# ExpositionTest.net
KiCad netlist of a schematic drawn in EAGLE
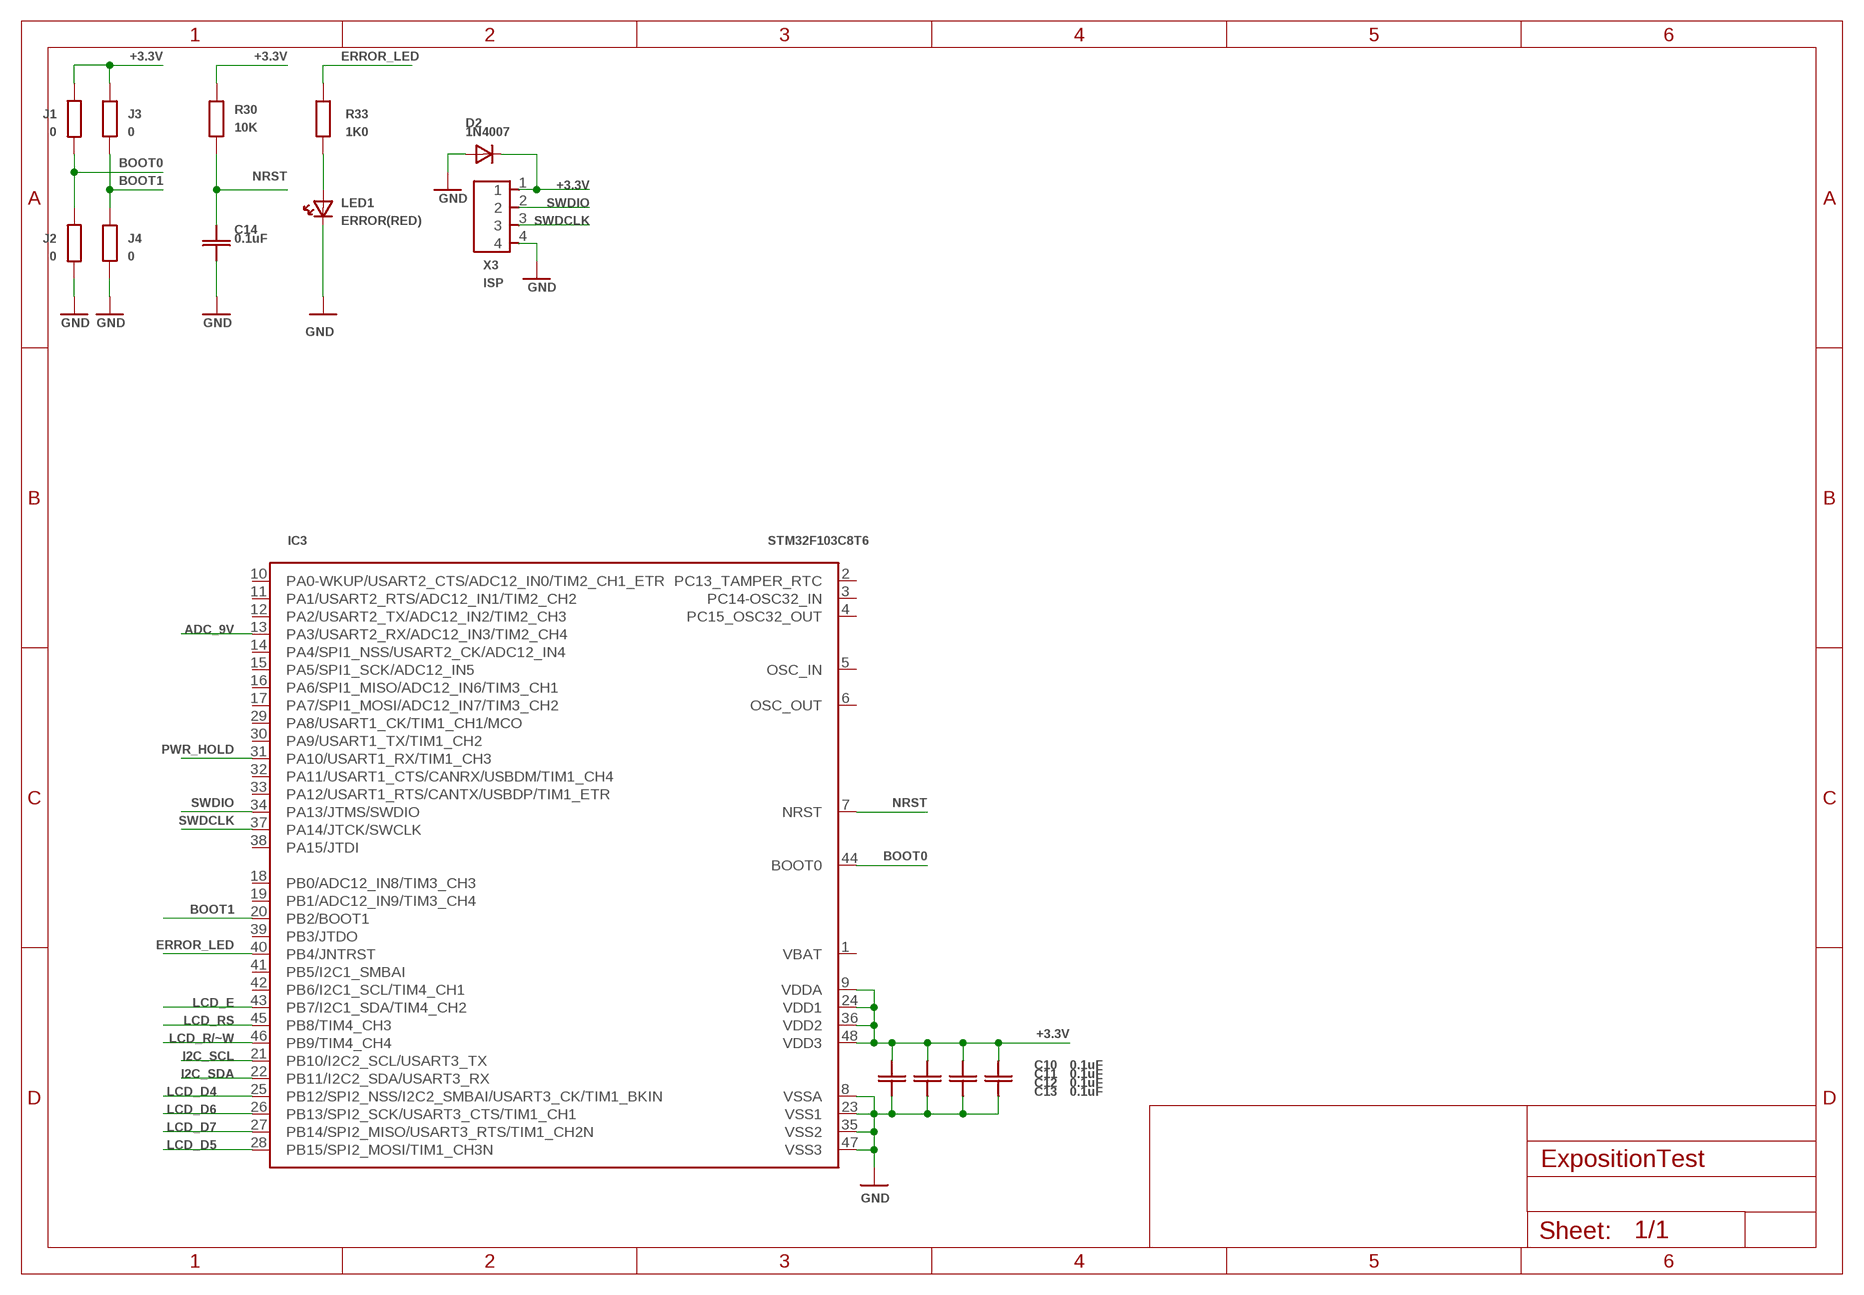
[diagram p0: schematic, sheet 1]

(export (version "E")
  (design (tool "Eeschema 10.0.6"))
  (components
    (comp (ref "C10")
      (value "0.1uF")
      (footprint "eagle-import:RSMD_0805")
      (libsource (lib "eagle-import") (part "CSMD_0805"))
    )
    (comp (ref "C11")
      (value "0.1uF")
      (footprint "eagle-import:RSMD_0805")
      (libsource (lib "eagle-import") (part "CSMD_0805"))
    )
    (comp (ref "C12")
      (value "0.1uF")
      (footprint "eagle-import:RSMD_0805")
      (libsource (lib "eagle-import") (part "CSMD_0805"))
    )
    (comp (ref "C13")
      (value "0.1uF")
      (footprint "eagle-import:RSMD_0805")
      (libsource (lib "eagle-import") (part "CSMD_0805"))
    )
    (comp (ref "C14")
      (value "0.1uF")
      (footprint "eagle-import:RSMD_0805")
      (libsource (lib "eagle-import") (part "CSMD_0805"))
    )
    (comp (ref "D2")
      (value "1N4007")
      (footprint "eagle-import:DO-41_10MM")
      (libsource (lib "eagle-import") (part "1N4001DO-41_10MM"))
    )
    (comp (ref "IC3")
      (value "STM32F103C8T6")
      (footprint "eagle-import:LQFP48")
      (libsource (lib "eagle-import") (part "STM32F103C8T6(LQFP48)(LQFP48)"))
    )
    (comp (ref "J1")
      (value "0")
      (footprint "eagle-import:RSMD_0805")
      (libsource (lib "eagle-import") (part "RSMD_0805"))
    )
    (comp (ref "J2")
      (value "0")
      (footprint "eagle-import:RSMD_0805")
      (libsource (lib "eagle-import") (part "RSMD_0805"))
    )
    (comp (ref "J3")
      (value "0")
      (footprint "eagle-import:RSMD_0805")
      (libsource (lib "eagle-import") (part "RSMD_0805"))
    )
    (comp (ref "J4")
      (value "0")
      (footprint "eagle-import:RSMD_0805")
      (libsource (lib "eagle-import") (part "RSMD_0805"))
    )
    (comp (ref "LED1")
      (value "ERROR(RED)")
      (footprint "eagle-import:LED_0805")
      (libsource (lib "eagle-import") (part "LED3MM(SMD0805)"))
    )
    (comp (ref "R30")
      (value "10K")
      (footprint "eagle-import:RSMD_0805")
      (libsource (lib "eagle-import") (part "RSMD_0805"))
    )
    (comp (ref "R33")
      (value "1K0")
      (footprint "eagle-import:RSMD_0805")
      (libsource (lib "eagle-import") (part "RSMD_0805"))
    )
    (comp (ref "X3")
      (value "ISP")
      (footprint "eagle-import:PIN4X1_2.54MM")
      (libsource (lib "eagle-import") (part "PIN4X1(2.54MM)"))
    )
  )
  (nets
    (net (code "1") (name "/+3.3V") (class "Default")
      (node (ref "C10") (pin "PAD_1") (pinfunction "PIN1_PAD_1") (pintype "bidirectional"))
      (node (ref "C11") (pin "PAD_1") (pinfunction "PIN1_PAD_1") (pintype "bidirectional"))
      (node (ref "C12") (pin "PAD_1") (pinfunction "PIN1_PAD_1") (pintype "bidirectional"))
      (node (ref "C13") (pin "PAD_1") (pinfunction "PIN1_PAD_1") (pintype "bidirectional"))
      (node (ref "D2") (pin "CATHODE") (pinfunction "CATHODE_CATHODE") (pintype "passive"))
      (node (ref "IC3") (pin "24") (pinfunction "VDD1_24") (pintype "bidirectional"))
      (node (ref "IC3") (pin "36") (pinfunction "VDD2_36") (pintype "bidirectional"))
      (node (ref "IC3") (pin "48") (pinfunction "VDD3_48") (pintype "bidirectional"))
      (node (ref "IC3") (pin "9") (pinfunction "VDDA_9") (pintype "bidirectional"))
      (node (ref "J1") (pin "PAD_0") (pinfunction "PIN0_PAD_0") (pintype "passive"))
      (node (ref "J3") (pin "PAD_0") (pinfunction "PIN0_PAD_0") (pintype "passive"))
      (node (ref "R30") (pin "PAD_0") (pinfunction "PIN0_PAD_0") (pintype "passive"))
      (node (ref "X3") (pin "1") (pinfunction "1_1") (pintype "bidirectional"))
    )
    (net (code "2") (name "/ADC_9V") (class "Default")
      (node (ref "IC3") (pin "13") (pinfunction "PA3/USART2_RX/ADC12_IN3/TIM2_CH4_13") (pintype "bidirectional"))
    )
    (net (code "3") (name "/BOOT0") (class "Default")
      (node (ref "IC3") (pin "44") (pinfunction "BOOT0_44") (pintype "bidirectional"))
      (node (ref "J1") (pin "PAD_1") (pinfunction "PIN1_PAD_1") (pintype "passive"))
      (node (ref "J2") (pin "PAD_0") (pinfunction "PIN0_PAD_0") (pintype "passive"))
    )
    (net (code "4") (name "/BOOT1") (class "Default")
      (node (ref "IC3") (pin "20") (pinfunction "PB2/BOOT1_20") (pintype "bidirectional"))
      (node (ref "J3") (pin "PAD_1") (pinfunction "PIN1_PAD_1") (pintype "passive"))
      (node (ref "J4") (pin "PAD_0") (pinfunction "PIN0_PAD_0") (pintype "passive"))
    )
    (net (code "5") (name "/ERROR_LED") (class "Default")
      (node (ref "IC3") (pin "40") (pinfunction "PB4/JNTRST_40") (pintype "bidirectional"))
      (node (ref "R33") (pin "PAD_0") (pinfunction "PIN0_PAD_0") (pintype "passive"))
    )
    (net (code "6") (name "/I2C_SCL") (class "Default")
      (node (ref "IC3") (pin "21") (pinfunction "PB10/I2C2_SCL/USART3_TX_21") (pintype "bidirectional"))
    )
    (net (code "7") (name "/I2C_SDA") (class "Default")
      (node (ref "IC3") (pin "22") (pinfunction "PB11/I2C2_SDA/USART3_RX_22") (pintype "bidirectional"))
    )
    (net (code "8") (name "/LCD_D4") (class "Default")
      (node (ref "IC3") (pin "25") (pinfunction "PB12/SPI2_NSS/I2C2_SMBAI/USART3_CK/TIM1_BKIN_25") (pintype "bidirectional"))
    )
    (net (code "9") (name "/LCD_D5") (class "Default")
      (node (ref "IC3") (pin "28") (pinfunction "PB15/SPI2_MOSI/TIM1_CH3N_28") (pintype "bidirectional"))
    )
    (net (code "10") (name "/LCD_D6") (class "Default")
      (node (ref "IC3") (pin "26") (pinfunction "PB13/SPI2_SCK/USART3_CTS/TIM1_CH1_26") (pintype "bidirectional"))
    )
    (net (code "11") (name "/LCD_D7") (class "Default")
      (node (ref "IC3") (pin "27") (pinfunction "PB14/SPI2_MISO/USART3_RTS/TIM1_CH2N_27") (pintype "bidirectional"))
    )
    (net (code "12") (name "/LCD_E") (class "Default")
      (node (ref "IC3") (pin "43") (pinfunction "PB7/I2C1_SDA/TIM4_CH2_43") (pintype "bidirectional"))
    )
    (net (code "13") (name "/LCD_RS") (class "Default")
      (node (ref "IC3") (pin "45") (pinfunction "PB8/TIM4_CH3_45") (pintype "bidirectional"))
    )
    (net (code "14") (name "/LCD_R{slash}~{W}") (class "Default")
      (node (ref "IC3") (pin "46") (pinfunction "PB9/TIM4_CH4_46") (pintype "bidirectional"))
    )
    (net (code "15") (name "/NRST") (class "Default")
      (node (ref "C14") (pin "PAD_1") (pinfunction "PIN1_PAD_1") (pintype "bidirectional"))
      (node (ref "IC3") (pin "7") (pinfunction "NRST_7") (pintype "bidirectional"))
      (node (ref "R30") (pin "PAD_1") (pinfunction "PIN1_PAD_1") (pintype "passive"))
    )
    (net (code "16") (name "/PWR_HOLD") (class "Default")
      (node (ref "IC3") (pin "31") (pinfunction "PA10/USART1_RX/TIM1_CH3_31") (pintype "bidirectional"))
    )
    (net (code "17") (name "/SWDCLK") (class "Default")
      (node (ref "IC3") (pin "37") (pinfunction "PA14/JTCK/SWCLK_37") (pintype "bidirectional"))
      (node (ref "X3") (pin "3") (pinfunction "3_3") (pintype "bidirectional"))
    )
    (net (code "18") (name "/SWDIO") (class "Default")
      (node (ref "IC3") (pin "34") (pinfunction "PA13/JTMS/SWDIO_34") (pintype "bidirectional"))
      (node (ref "X3") (pin "2") (pinfunction "2_2") (pintype "bidirectional"))
    )
    (net (code "19") (name "GND") (class "Default")
      (node (ref "C10") (pin "PAD_0") (pinfunction "PIN0_PAD_0") (pintype "bidirectional"))
      (node (ref "C11") (pin "PAD_0") (pinfunction "PIN0_PAD_0") (pintype "bidirectional"))
      (node (ref "C12") (pin "PAD_0") (pinfunction "PIN0_PAD_0") (pintype "bidirectional"))
      (node (ref "C13") (pin "PAD_0") (pinfunction "PIN0_PAD_0") (pintype "bidirectional"))
      (node (ref "C14") (pin "PAD_0") (pinfunction "PIN0_PAD_0") (pintype "bidirectional"))
      (node (ref "D2") (pin "ANODE") (pinfunction "ANODE_ANODE") (pintype "passive"))
      (node (ref "IC3") (pin "23") (pinfunction "VSS1_23") (pintype "bidirectional"))
      (node (ref "IC3") (pin "35") (pinfunction "VSS2_35") (pintype "bidirectional"))
      (node (ref "IC3") (pin "47") (pinfunction "VSS3_47") (pintype "bidirectional"))
      (node (ref "IC3") (pin "8") (pinfunction "VSSA_8") (pintype "bidirectional"))
      (node (ref "J2") (pin "PAD_1") (pinfunction "PIN1_PAD_1") (pintype "passive"))
      (node (ref "J4") (pin "PAD_1") (pinfunction "PIN1_PAD_1") (pintype "passive"))
      (node (ref "LED1") (pin "CATHODE") (pinfunction "CATHODE_CATHODE") (pintype "passive"))
      (node (ref "X3") (pin "4") (pinfunction "4_4") (pintype "bidirectional"))
    )
    (net (code "20") (name "Net-(R33-PIN1)") (class "Default")
      (node (ref "LED1") (pin "ANODE") (pinfunction "ANODE_ANODE") (pintype "passive"))
      (node (ref "R33") (pin "PAD_1") (pinfunction "PIN1_PAD_1") (pintype "passive"))
    )
    (net (code "21") (name "unconnected-(IC3-OSC_IN-Pad5)") (class "Default")
      (node (ref "IC3") (pin "5") (pinfunction "OSC_IN_5") (pintype "bidirectional"))
    )
    (net (code "22") (name "unconnected-(IC3-OSC_OUT-Pad6)") (class "Default")
      (node (ref "IC3") (pin "6") (pinfunction "OSC_OUT_6") (pintype "bidirectional"))
    )
    (net (code "23") (name "unconnected-(IC3-PA0-WKUP{slash}USART2_CTS{slash}ADC12_IN0{slash}TIM2_CH1_ETR-Pad10)") (class "Default")
      (node (ref "IC3") (pin "10") (pinfunction "PA0-WKUP/USART2_CTS/ADC12_IN0/TIM2_CH1_ETR_10") (pintype "bidirectional"))
    )
    (net (code "24") (name "unconnected-(IC3-PA1{slash}USART2_RTS{slash}ADC12_IN1{slash}TIM2_CH2-Pad11)") (class "Default")
      (node (ref "IC3") (pin "11") (pinfunction "PA1/USART2_RTS/ADC12_IN1/TIM2_CH2_11") (pintype "bidirectional"))
    )
    (net (code "25") (name "unconnected-(IC3-PA2{slash}USART2_TX{slash}ADC12_IN2{slash}TIM2_CH3-Pad12)") (class "Default")
      (node (ref "IC3") (pin "12") (pinfunction "PA2/USART2_TX/ADC12_IN2/TIM2_CH3_12") (pintype "bidirectional"))
    )
    (net (code "26") (name "unconnected-(IC3-PA4{slash}SPI1_NSS{slash}USART2_CK{slash}ADC12_IN4-Pad14)") (class "Default")
      (node (ref "IC3") (pin "14") (pinfunction "PA4/SPI1_NSS/USART2_CK/ADC12_IN4_14") (pintype "bidirectional"))
    )
    (net (code "27") (name "unconnected-(IC3-PA5{slash}SPI1_SCK{slash}ADC12_IN5-Pad15)") (class "Default")
      (node (ref "IC3") (pin "15") (pinfunction "PA5/SPI1_SCK/ADC12_IN5_15") (pintype "bidirectional"))
    )
    (net (code "28") (name "unconnected-(IC3-PA6{slash}SPI1_MISO{slash}ADC12_IN6{slash}TIM3_CH1-Pad16)") (class "Default")
      (node (ref "IC3") (pin "16") (pinfunction "PA6/SPI1_MISO/ADC12_IN6/TIM3_CH1_16") (pintype "bidirectional"))
    )
    (net (code "29") (name "unconnected-(IC3-PA7{slash}SPI1_MOSI{slash}ADC12_IN7{slash}TIM3_CH2-Pad17)") (class "Default")
      (node (ref "IC3") (pin "17") (pinfunction "PA7/SPI1_MOSI/ADC12_IN7/TIM3_CH2_17") (pintype "bidirectional"))
    )
    (net (code "30") (name "unconnected-(IC3-PA8{slash}USART1_CK{slash}TIM1_CH1{slash}MCO-Pad29)") (class "Default")
      (node (ref "IC3") (pin "29") (pinfunction "PA8/USART1_CK/TIM1_CH1/MCO_29") (pintype "bidirectional"))
    )
    (net (code "31") (name "unconnected-(IC3-PA9{slash}USART1_TX{slash}TIM1_CH2-Pad30)") (class "Default")
      (node (ref "IC3") (pin "30") (pinfunction "PA9/USART1_TX/TIM1_CH2_30") (pintype "bidirectional"))
    )
    (net (code "32") (name "unconnected-(IC3-PA11{slash}USART1_CTS{slash}CANRX{slash}USBDM{slash}TIM1_CH4-Pad32)") (class "Default")
      (node (ref "IC3") (pin "32") (pinfunction "PA11/USART1_CTS/CANRX/USBDM/TIM1_CH4_32") (pintype "bidirectional"))
    )
    (net (code "33") (name "unconnected-(IC3-PA12{slash}USART1_RTS{slash}CANTX{slash}USBDP{slash}TIM1_ETR-Pad33)") (class "Default")
      (node (ref "IC3") (pin "33") (pinfunction "PA12/USART1_RTS/CANTX/USBDP/TIM1_ETR_33") (pintype "bidirectional"))
    )
    (net (code "34") (name "unconnected-(IC3-PA15{slash}JTDI-Pad38)") (class "Default")
      (node (ref "IC3") (pin "38") (pinfunction "PA15/JTDI_38") (pintype "bidirectional"))
    )
    (net (code "35") (name "unconnected-(IC3-PB0{slash}ADC12_IN8{slash}TIM3_CH3-Pad18)") (class "Default")
      (node (ref "IC3") (pin "18") (pinfunction "PB0/ADC12_IN8/TIM3_CH3_18") (pintype "bidirectional"))
    )
    (net (code "36") (name "unconnected-(IC3-PB1{slash}ADC12_IN9{slash}TIM3_CH4-Pad19)") (class "Default")
      (node (ref "IC3") (pin "19") (pinfunction "PB1/ADC12_IN9/TIM3_CH4_19") (pintype "bidirectional"))
    )
    (net (code "37") (name "unconnected-(IC3-PB3{slash}JTDO-Pad39)") (class "Default")
      (node (ref "IC3") (pin "39") (pinfunction "PB3/JTDO_39") (pintype "bidirectional"))
    )
    (net (code "38") (name "unconnected-(IC3-PB5{slash}I2C1_SMBAI-Pad41)") (class "Default")
      (node (ref "IC3") (pin "41") (pinfunction "PB5/I2C1_SMBAI_41") (pintype "bidirectional"))
    )
    (net (code "39") (name "unconnected-(IC3-PB6{slash}I2C1_SCL{slash}TIM4_CH1-Pad42)") (class "Default")
      (node (ref "IC3") (pin "42") (pinfunction "PB6/I2C1_SCL/TIM4_CH1_42") (pintype "bidirectional"))
    )
    (net (code "40") (name "unconnected-(IC3-PC13_TAMPER_RTC-Pad2)") (class "Default")
      (node (ref "IC3") (pin "2") (pinfunction "PC13_TAMPER_RTC_2") (pintype "bidirectional"))
    )
    (net (code "41") (name "unconnected-(IC3-PC14-OSC32_IN-Pad3)") (class "Default")
      (node (ref "IC3") (pin "3") (pinfunction "PC14-OSC32_IN_3") (pintype "bidirectional"))
    )
    (net (code "42") (name "unconnected-(IC3-PC15_OSC32_OUT-Pad4)") (class "Default")
      (node (ref "IC3") (pin "4") (pinfunction "PC15_OSC32_OUT_4") (pintype "bidirectional"))
    )
    (net (code "43") (name "unconnected-(IC3-VBAT-Pad1)") (class "Default")
      (node (ref "IC3") (pin "1") (pinfunction "VBAT_1") (pintype "bidirectional"))
    )
  )
)
